# Microcontroller_board_Photodiode_plate.net
KiCad netlist of a schematic drawn in EasyEDA
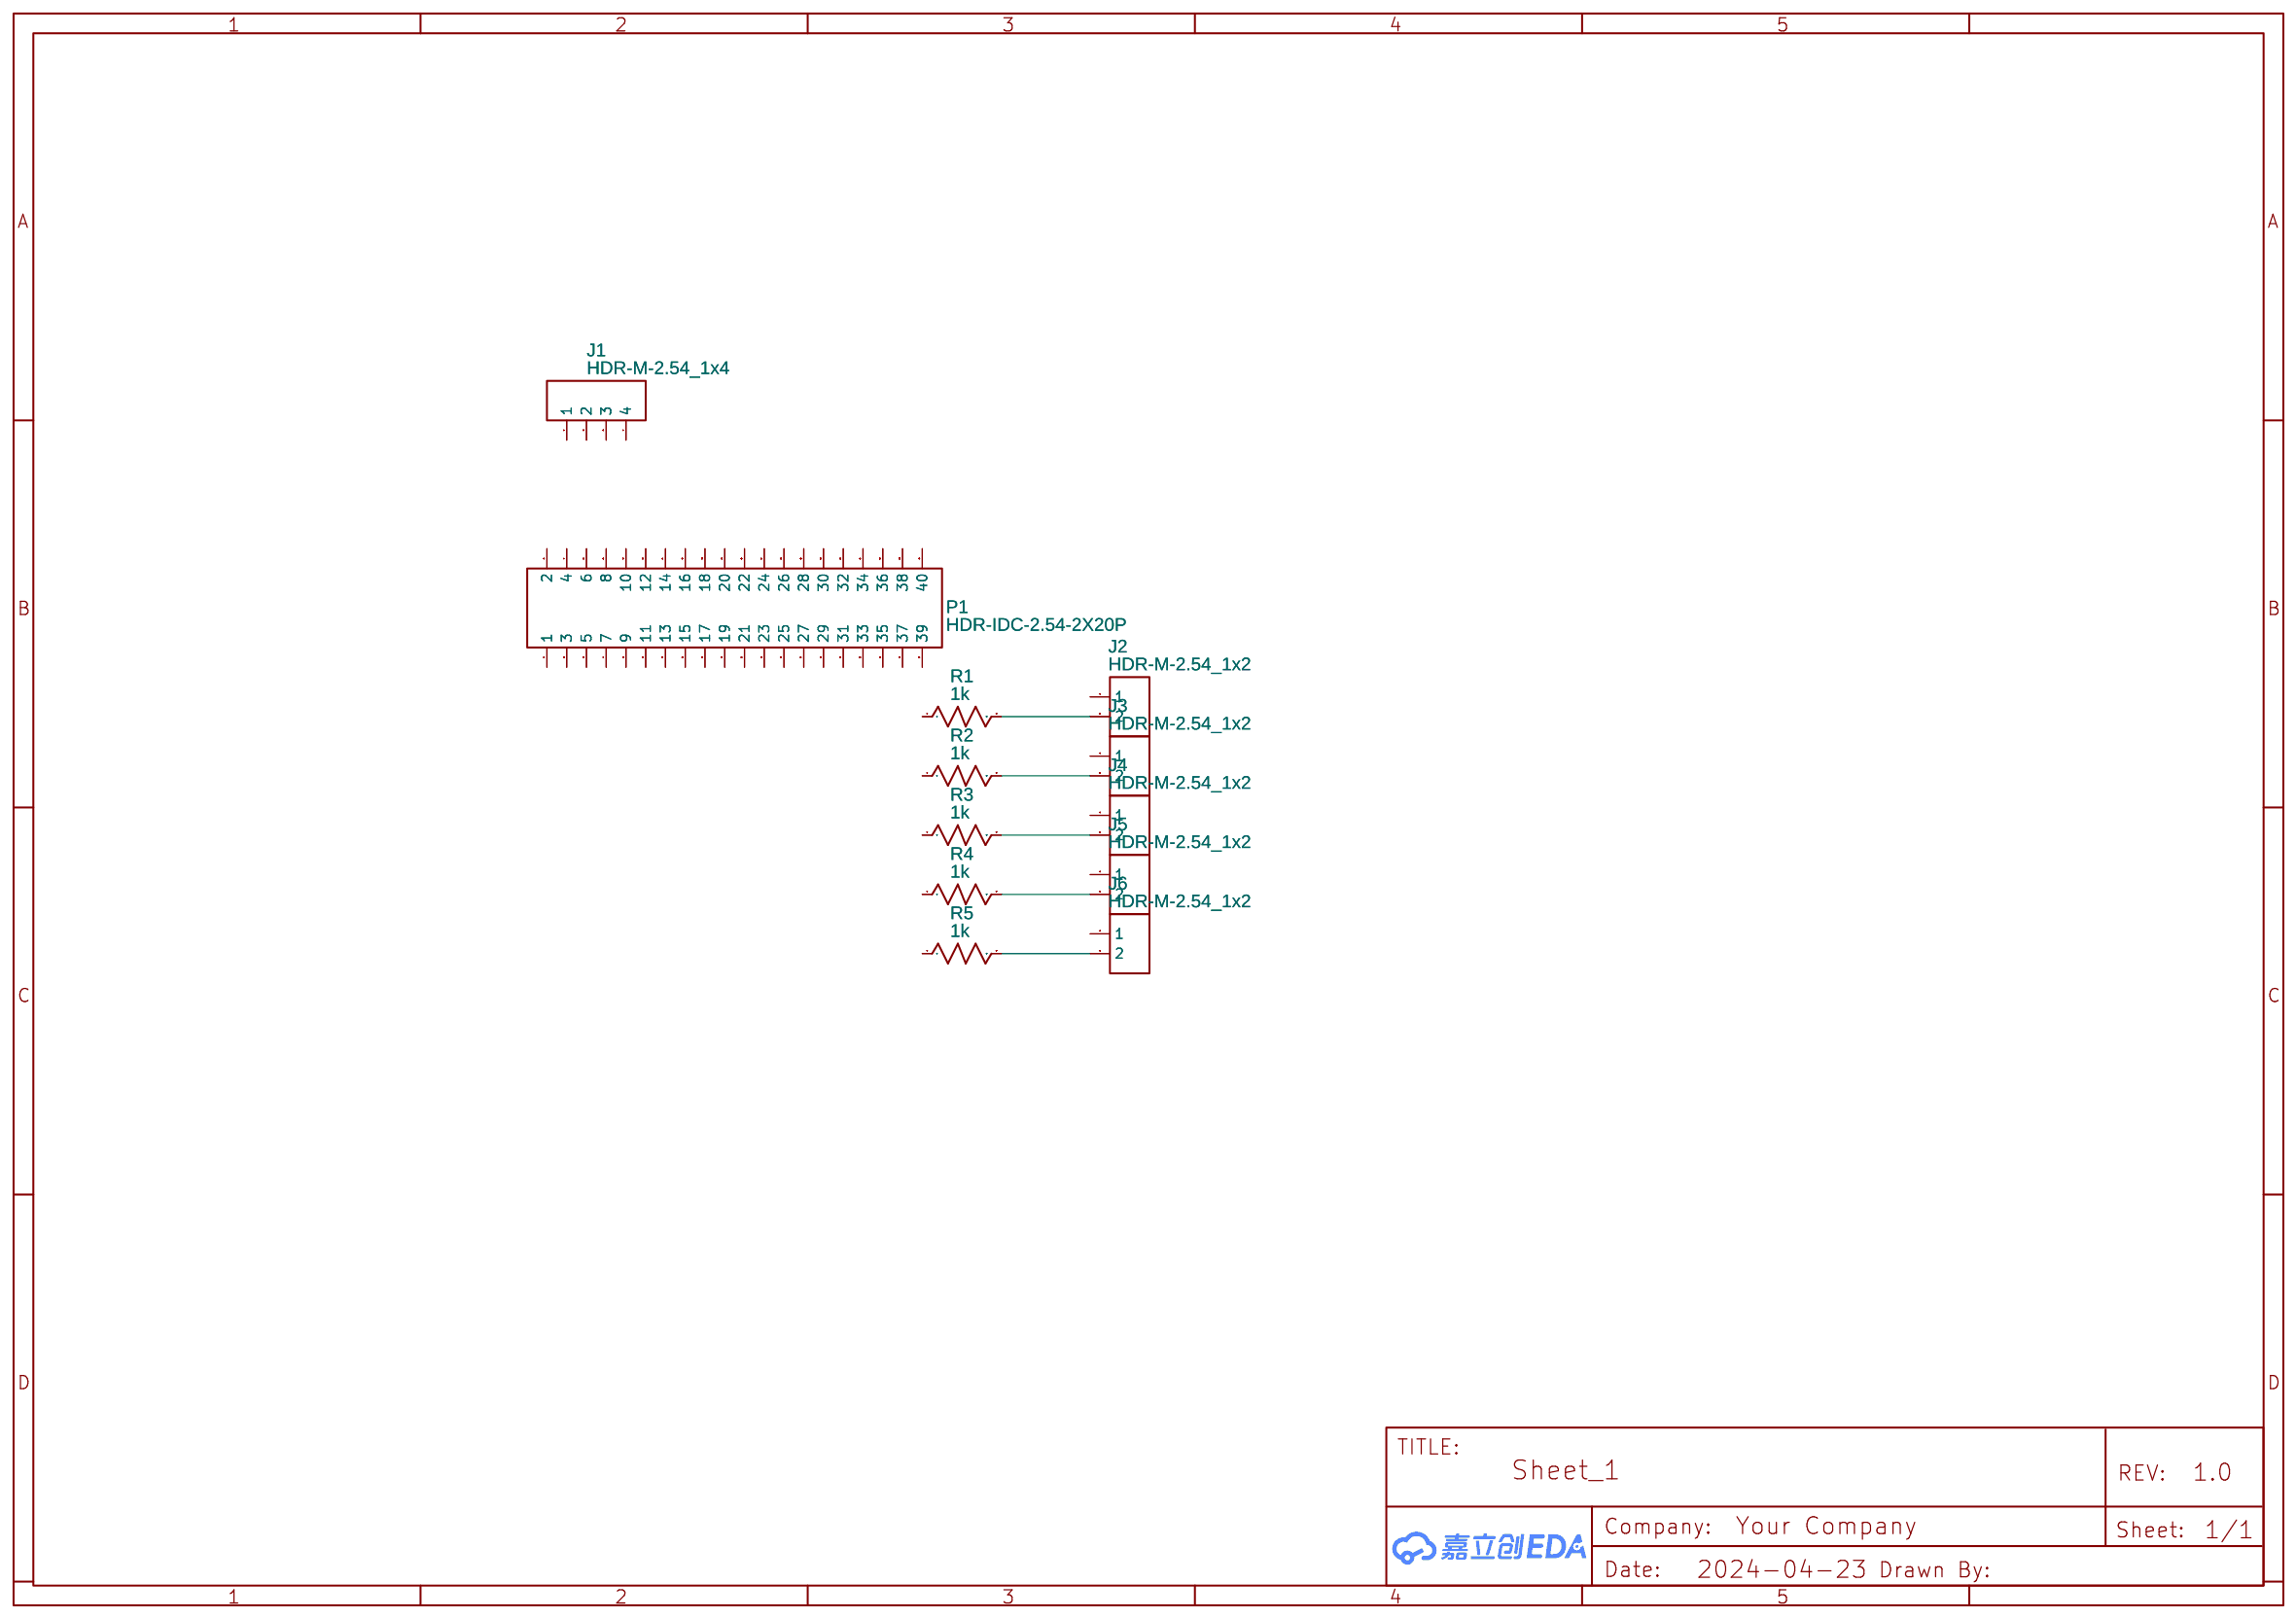
[diagram p0: schematic sheet]

(export (version "E")
  (design (tool "Eeschema 10.0.6"))
  (components
    (comp (ref "J1")
      (value "HDR-M-2.54_1x4")
      (fields (field (name "BOM_Supplier Part") "C124378"))
      (libsource (lib "") (part "HDR-M-2.54_1x4"))
    )
    (comp (ref "J2")
      (value "HDR-M-2.54_1x2")
      (fields (field (name "BOM_Supplier Part") "C124375"))
      (libsource (lib "") (part "HDR-M-2.54_1x2"))
    )
    (comp (ref "J3")
      (value "HDR-M-2.54_1x2")
      (fields (field (name "BOM_Supplier Part") "C124375"))
      (libsource (lib "") (part "HDR-M-2.54_1x2"))
    )
    (comp (ref "J4")
      (value "HDR-M-2.54_1x2")
      (fields (field (name "BOM_Supplier Part") "C124375"))
      (libsource (lib "") (part "HDR-M-2.54_1x2"))
    )
    (comp (ref "J5")
      (value "HDR-M-2.54_1x2")
      (fields (field (name "BOM_Supplier Part") "C124375"))
      (libsource (lib "") (part "HDR-M-2.54_1x2"))
    )
    (comp (ref "J6")
      (value "HDR-M-2.54_1x2")
      (fields (field (name "BOM_Supplier Part") "C124375"))
      (libsource (lib "") (part "HDR-M-2.54_1x2"))
    )
    (comp (ref "P1")
      (value "HDR-IDC-2.54-2X20P")
      (fields
        (field (name "BOM_Manufacturer Part") "IDC Box 2X20 2.54MM")
        (field (name "BOM_Supplier Part") "C9138")
      )
      (libsource (lib "") (part "HDR-IDC-2.54-2X20P"))
    )
    (comp (ref "R1") (value "1k") (libsource (lib "") (part "R_0603_US")))
    (comp (ref "R2") (value "1k") (libsource (lib "") (part "R_0603_US")))
    (comp (ref "R3") (value "1k") (libsource (lib "") (part "R_0603_US")))
    (comp (ref "R4") (value "1k") (libsource (lib "") (part "R_0603_US")))
    (comp (ref "R5") (value "1k") (libsource (lib "") (part "R_0603_US")))
  )
  (nets
    (net (code "1") (name "Net-(J2-Pad2)") (class "Default")
      (node (ref "J2") (pin "2") (pinfunction "2_2") (pintype "unspecified"))
      (node (ref "R1") (pin "2") (pinfunction "2_2") (pintype "unspecified"))
    )
    (net (code "2") (name "Net-(J3-Pad2)") (class "Default")
      (node (ref "J3") (pin "2") (pinfunction "2_2") (pintype "unspecified"))
      (node (ref "R2") (pin "2") (pinfunction "2_2") (pintype "unspecified"))
    )
    (net (code "3") (name "Net-(J4-Pad2)") (class "Default")
      (node (ref "J4") (pin "2") (pinfunction "2_2") (pintype "unspecified"))
      (node (ref "R3") (pin "2") (pinfunction "2_2") (pintype "unspecified"))
    )
    (net (code "4") (name "Net-(J5-Pad2)") (class "Default")
      (node (ref "J5") (pin "2") (pinfunction "2_2") (pintype "unspecified"))
      (node (ref "R4") (pin "2") (pinfunction "2_2") (pintype "unspecified"))
    )
    (net (code "5") (name "Net-(J6-Pad2)") (class "Default")
      (node (ref "J6") (pin "2") (pinfunction "2_2") (pintype "unspecified"))
      (node (ref "R5") (pin "2") (pinfunction "2_2") (pintype "unspecified"))
    )
    (net (code "6") (name "unconnected-(J1-Pad1)") (class "Default")
      (node (ref "J1") (pin "1") (pinfunction "1_1") (pintype "unspecified"))
    )
    (net (code "7") (name "unconnected-(J1-Pad2)") (class "Default")
      (node (ref "J1") (pin "2") (pinfunction "2_2") (pintype "unspecified"))
    )
    (net (code "8") (name "unconnected-(J1-Pad3)") (class "Default")
      (node (ref "J1") (pin "3") (pinfunction "3_3") (pintype "unspecified"))
    )
    (net (code "9") (name "unconnected-(J1-Pad4)") (class "Default")
      (node (ref "J1") (pin "4") (pinfunction "4_4") (pintype "unspecified"))
    )
    (net (code "10") (name "unconnected-(J2-Pad1)") (class "Default")
      (node (ref "J2") (pin "1") (pinfunction "1_1") (pintype "unspecified"))
    )
    (net (code "11") (name "unconnected-(J3-Pad1)") (class "Default")
      (node (ref "J3") (pin "1") (pinfunction "1_1") (pintype "unspecified"))
    )
    (net (code "12") (name "unconnected-(J4-Pad1)") (class "Default")
      (node (ref "J4") (pin "1") (pinfunction "1_1") (pintype "unspecified"))
    )
    (net (code "13") (name "unconnected-(J5-Pad1)") (class "Default")
      (node (ref "J5") (pin "1") (pinfunction "1_1") (pintype "unspecified"))
    )
    (net (code "14") (name "unconnected-(J6-Pad1)") (class "Default")
      (node (ref "J6") (pin "1") (pinfunction "1_1") (pintype "unspecified"))
    )
    (net (code "15") (name "unconnected-(P1-Pad1)") (class "Default")
      (node (ref "P1") (pin "1") (pinfunction "1_1") (pintype "unspecified"))
    )
    (net (code "16") (name "unconnected-(P1-Pad2)") (class "Default")
      (node (ref "P1") (pin "2") (pinfunction "2_2") (pintype "unspecified"))
    )
    (net (code "17") (name "unconnected-(P1-Pad3)") (class "Default")
      (node (ref "P1") (pin "3") (pinfunction "3_3") (pintype "unspecified"))
    )
    (net (code "18") (name "unconnected-(P1-Pad4)") (class "Default")
      (node (ref "P1") (pin "4") (pinfunction "4_4") (pintype "unspecified"))
    )
    (net (code "19") (name "unconnected-(P1-Pad5)") (class "Default")
      (node (ref "P1") (pin "5") (pinfunction "5_5") (pintype "unspecified"))
    )
    (net (code "20") (name "unconnected-(P1-Pad6)") (class "Default")
      (node (ref "P1") (pin "6") (pinfunction "6_6") (pintype "unspecified"))
    )
    (net (code "21") (name "unconnected-(P1-Pad7)") (class "Default")
      (node (ref "P1") (pin "7") (pinfunction "7_7") (pintype "unspecified"))
    )
    (net (code "22") (name "unconnected-(P1-Pad8)") (class "Default")
      (node (ref "P1") (pin "8") (pinfunction "8_8") (pintype "unspecified"))
    )
    (net (code "23") (name "unconnected-(P1-Pad9)") (class "Default")
      (node (ref "P1") (pin "9") (pinfunction "9_9") (pintype "unspecified"))
    )
    (net (code "24") (name "unconnected-(P1-Pad10)") (class "Default")
      (node (ref "P1") (pin "10") (pinfunction "10_10") (pintype "unspecified"))
    )
    (net (code "25") (name "unconnected-(P1-Pad11)") (class "Default")
      (node (ref "P1") (pin "11") (pinfunction "11_11") (pintype "unspecified"))
    )
    (net (code "26") (name "unconnected-(P1-Pad12)") (class "Default")
      (node (ref "P1") (pin "12") (pinfunction "12_12") (pintype "unspecified"))
    )
    (net (code "27") (name "unconnected-(P1-Pad13)") (class "Default")
      (node (ref "P1") (pin "13") (pinfunction "13_13") (pintype "unspecified"))
    )
    (net (code "28") (name "unconnected-(P1-Pad14)") (class "Default")
      (node (ref "P1") (pin "14") (pinfunction "14_14") (pintype "unspecified"))
    )
    (net (code "29") (name "unconnected-(P1-Pad15)") (class "Default")
      (node (ref "P1") (pin "15") (pinfunction "15_15") (pintype "unspecified"))
    )
    (net (code "30") (name "unconnected-(P1-Pad16)") (class "Default")
      (node (ref "P1") (pin "16") (pinfunction "16_16") (pintype "unspecified"))
    )
    (net (code "31") (name "unconnected-(P1-Pad17)") (class "Default")
      (node (ref "P1") (pin "17") (pinfunction "17_17") (pintype "unspecified"))
    )
    (net (code "32") (name "unconnected-(P1-Pad18)") (class "Default")
      (node (ref "P1") (pin "18") (pinfunction "18_18") (pintype "unspecified"))
    )
    (net (code "33") (name "unconnected-(P1-Pad19)") (class "Default")
      (node (ref "P1") (pin "19") (pinfunction "19_19") (pintype "unspecified"))
    )
    (net (code "34") (name "unconnected-(P1-Pad20)") (class "Default")
      (node (ref "P1") (pin "20") (pinfunction "20_20") (pintype "unspecified"))
    )
    (net (code "35") (name "unconnected-(P1-Pad21)") (class "Default")
      (node (ref "P1") (pin "21") (pinfunction "21_21") (pintype "unspecified"))
    )
    (net (code "36") (name "unconnected-(P1-Pad22)") (class "Default")
      (node (ref "P1") (pin "22") (pinfunction "22_22") (pintype "unspecified"))
    )
    (net (code "37") (name "unconnected-(P1-Pad23)") (class "Default")
      (node (ref "P1") (pin "23") (pinfunction "23_23") (pintype "unspecified"))
    )
    (net (code "38") (name "unconnected-(P1-Pad24)") (class "Default")
      (node (ref "P1") (pin "24") (pinfunction "24_24") (pintype "unspecified"))
    )
    (net (code "39") (name "unconnected-(P1-Pad25)") (class "Default")
      (node (ref "P1") (pin "25") (pinfunction "25_25") (pintype "unspecified"))
    )
    (net (code "40") (name "unconnected-(P1-Pad26)") (class "Default")
      (node (ref "P1") (pin "26") (pinfunction "26_26") (pintype "unspecified"))
    )
    (net (code "41") (name "unconnected-(P1-Pad27)") (class "Default")
      (node (ref "P1") (pin "27") (pinfunction "27_27") (pintype "unspecified"))
    )
    (net (code "42") (name "unconnected-(P1-Pad28)") (class "Default")
      (node (ref "P1") (pin "28") (pinfunction "28_28") (pintype "unspecified"))
    )
    (net (code "43") (name "unconnected-(P1-Pad29)") (class "Default")
      (node (ref "P1") (pin "29") (pinfunction "29_29") (pintype "unspecified"))
    )
    (net (code "44") (name "unconnected-(P1-Pad30)") (class "Default")
      (node (ref "P1") (pin "30") (pinfunction "30_30") (pintype "unspecified"))
    )
    (net (code "45") (name "unconnected-(P1-Pad31)") (class "Default")
      (node (ref "P1") (pin "31") (pinfunction "31_31") (pintype "unspecified"))
    )
    (net (code "46") (name "unconnected-(P1-Pad32)") (class "Default")
      (node (ref "P1") (pin "32") (pinfunction "32_32") (pintype "unspecified"))
    )
    (net (code "47") (name "unconnected-(P1-Pad33)") (class "Default")
      (node (ref "P1") (pin "33") (pinfunction "33_33") (pintype "unspecified"))
    )
    (net (code "48") (name "unconnected-(P1-Pad34)") (class "Default")
      (node (ref "P1") (pin "34") (pinfunction "34_34") (pintype "unspecified"))
    )
    (net (code "49") (name "unconnected-(P1-Pad35)") (class "Default")
      (node (ref "P1") (pin "35") (pinfunction "35_35") (pintype "unspecified"))
    )
    (net (code "50") (name "unconnected-(P1-Pad36)") (class "Default")
      (node (ref "P1") (pin "36") (pinfunction "36_36") (pintype "unspecified"))
    )
    (net (code "51") (name "unconnected-(P1-Pad37)") (class "Default")
      (node (ref "P1") (pin "37") (pinfunction "37_37") (pintype "unspecified"))
    )
    (net (code "52") (name "unconnected-(P1-Pad38)") (class "Default")
      (node (ref "P1") (pin "38") (pinfunction "38_38") (pintype "unspecified"))
    )
    (net (code "53") (name "unconnected-(P1-Pad39)") (class "Default")
      (node (ref "P1") (pin "39") (pinfunction "39_39") (pintype "unspecified"))
    )
    (net (code "54") (name "unconnected-(P1-Pad40)") (class "Default")
      (node (ref "P1") (pin "40") (pinfunction "40_40") (pintype "unspecified"))
    )
    (net (code "55") (name "unconnected-(R1-Pad1)") (class "Default")
      (node (ref "R1") (pin "1") (pinfunction "1_1") (pintype "unspecified"))
    )
    (net (code "56") (name "unconnected-(R2-Pad1)") (class "Default")
      (node (ref "R2") (pin "1") (pinfunction "1_1") (pintype "unspecified"))
    )
    (net (code "57") (name "unconnected-(R3-Pad1)") (class "Default")
      (node (ref "R3") (pin "1") (pinfunction "1_1") (pintype "unspecified"))
    )
    (net (code "58") (name "unconnected-(R4-Pad1)") (class "Default")
      (node (ref "R4") (pin "1") (pinfunction "1_1") (pintype "unspecified"))
    )
    (net (code "59") (name "unconnected-(R5-Pad1)") (class "Default")
      (node (ref "R5") (pin "1") (pinfunction "1_1") (pintype "unspecified"))
    )
  )
)
